# TraitementAnalogique.net
KiCad netlist of a schematic drawn in Altium Designer
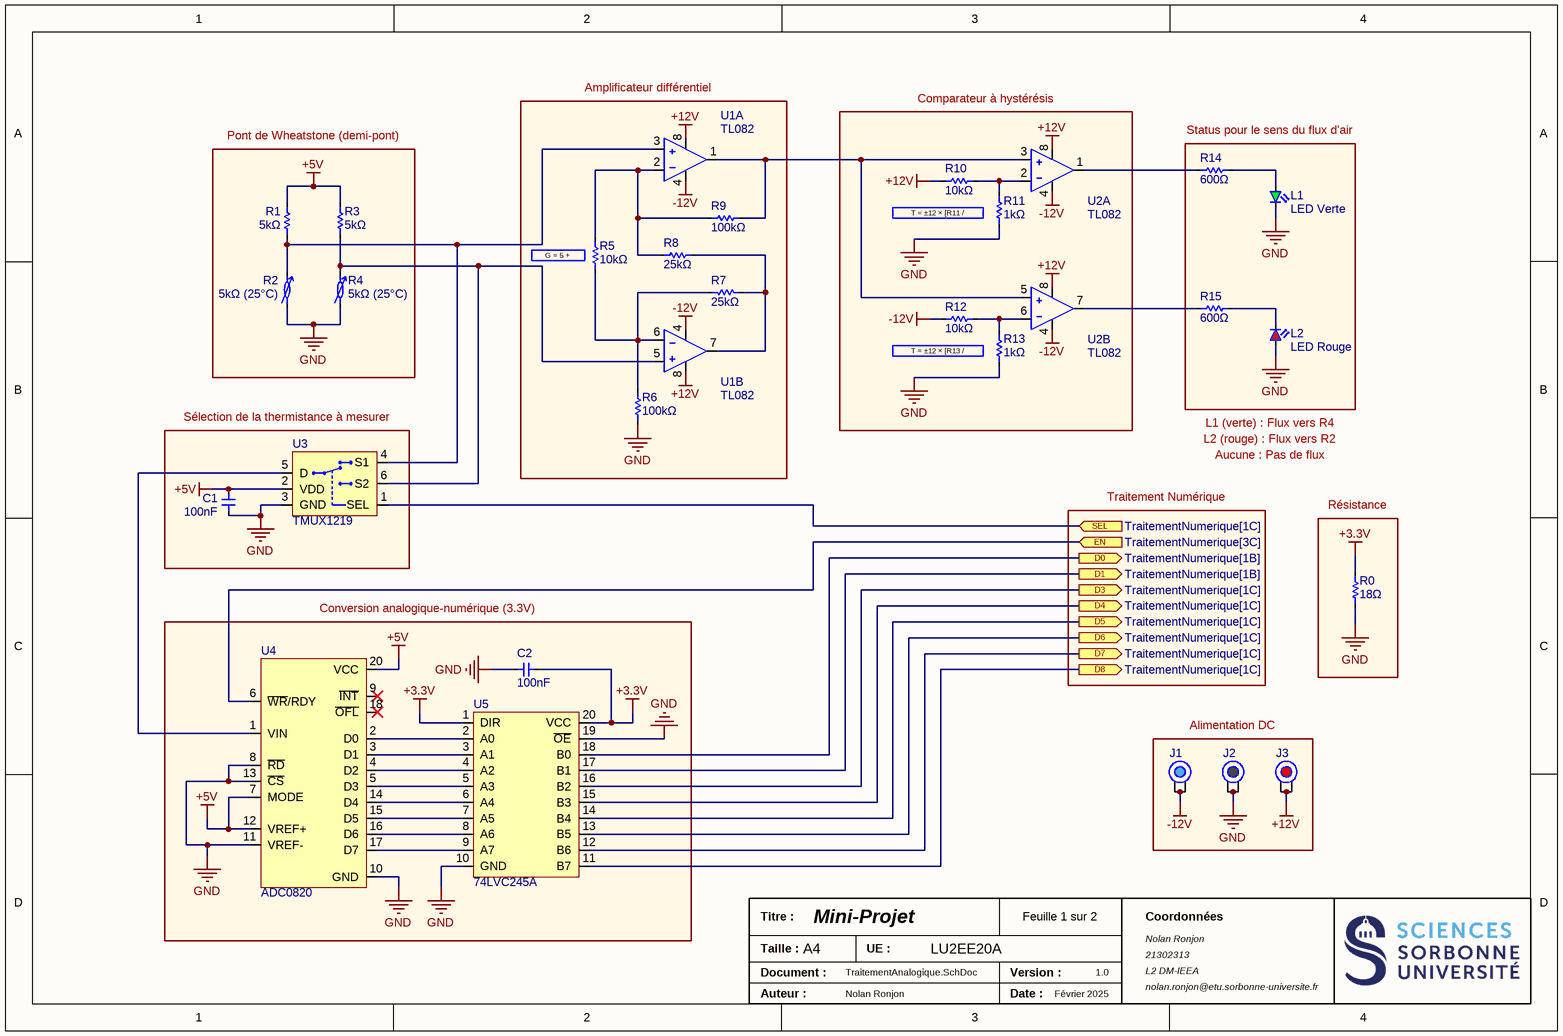
[diagram p0: TraitementAnalogique.SchDoc]

(export (version "E")
  (design (tool "Eeschema 10.0.6"))
  (components
    (comp (ref "C1")
      (value "100nF")
      (footprint "0603")
      (description "Condensateur")
      (libsource (lib "LU2EE20A") (part "Condensateur"))
    )
    (comp (ref "C2")
      (value "100nF")
      (footprint "0603")
      (description "Condensateur")
      (libsource (lib "LU2EE20A") (part "Condensateur"))
    )
    (comp (ref "J1")
      (value "Fiche Banane")
      (footprint "Fiche Banane")
      (description "Connecteur")
      (fields (field (name "MANUFACTURER PART") "24.243.5") (field (name "JLCPCB PART") "C7437325"))
      (libsource (lib "LU2EE20A") (part "Fiche Banane"))
    )
    (comp (ref "J2")
      (value "Fiche Banane")
      (footprint "Fiche Banane")
      (description "Connecteur")
      (fields (field (name "MANUFACTURER PART") "24.243.2") (field (name "JLCPCB PART") "C7437322"))
      (libsource (lib "LU2EE20A") (part "Fiche Banane"))
    )
    (comp (ref "J3")
      (value "Fiche Banane")
      (footprint "Fiche Banane")
      (description "Connecteur")
      (fields (field (name "MANUFACTURER PART") "24.243.1") (field (name "JLCPCB PART") "C7437321"))
      (libsource (lib "LU2EE20A") (part "Fiche Banane"))
    )
    (comp (ref "L1")
      (value "LED Verte")
      (footprint "0603 (Pol)")
      (description "LED")
      (fields (field (name "MANUFACTURER PART") "XL-1608UGC-04") (field (name "JLCPCB PART") "C965804"))
      (libsource (lib "LU2EE20A") (part "LED Verte"))
    )
    (comp (ref "L2")
      (value "LED Rouge")
      (footprint "0603 (Pol)")
      (description "LED")
      (fields (field (name "MANUFACTURER PART") "XL-1608SURC-06") (field (name "JLCPCB PART") "C965799"))
      (libsource (lib "LU2EE20A") (part "LED Rouge"))
    )
    (comp (ref "R0")
      (value "18Ω")
      (footprint "Bornier")
      (description "Resistance")
      (fields (field (name "MANUFACTURER PART") "WJ500V-5.08-2P") (field (name "JLCPCB PART") "C8465"))
      (libsource (lib "LU2EE20A") (part "Resistance"))
    )
    (comp (ref "R1")
      (value "5kΩ")
      (footprint "0603")
      (description "Resistance")
      (libsource (lib "LU2EE20A") (part "Resistance"))
    )
    (comp (ref "R2")
      (value "5kΩ (25°C)")
      (footprint "Bornier")
      (description "Thermistance")
      (fields (field (name "MANUFACTURER PART") "WJ500V-5.08-2P") (field (name "JLCPCB PART") "C8465"))
      (libsource (lib "LU2EE20A") (part "CTN"))
    )
    (comp (ref "R3")
      (value "5kΩ")
      (footprint "0603")
      (description "Resistance")
      (libsource (lib "LU2EE20A") (part "Resistance"))
    )
    (comp (ref "R4")
      (value "5kΩ (25°C)")
      (footprint "Bornier")
      (description "Thermistance")
      (fields (field (name "MANUFACTURER PART") "WJ500V-5.08-2P") (field (name "JLCPCB PART") "C8465"))
      (libsource (lib "LU2EE20A") (part "CTN"))
    )
    (comp (ref "R5")
      (value "10kΩ")
      (footprint "0603")
      (description "Resistance")
      (libsource (lib "LU2EE20A") (part "Resistance"))
    )
    (comp (ref "R6")
      (value "100kΩ")
      (footprint "0603")
      (description "Resistance")
      (libsource (lib "LU2EE20A") (part "Resistance"))
    )
    (comp (ref "R7")
      (value "25kΩ")
      (footprint "0603")
      (description "Resistance")
      (libsource (lib "LU2EE20A") (part "Resistance"))
    )
    (comp (ref "R8")
      (value "25kΩ")
      (footprint "0603")
      (description "Resistance")
      (libsource (lib "LU2EE20A") (part "Resistance"))
    )
    (comp (ref "R9")
      (value "100kΩ")
      (footprint "0603")
      (description "Resistance")
      (libsource (lib "LU2EE20A") (part "Resistance"))
    )
    (comp (ref "R10")
      (value "10kΩ")
      (footprint "0603")
      (description "Resistance")
      (libsource (lib "LU2EE20A") (part "Resistance"))
    )
    (comp (ref "R11")
      (value "1kΩ")
      (footprint "0603")
      (description "Resistance")
      (libsource (lib "LU2EE20A") (part "Resistance"))
    )
    (comp (ref "R12")
      (value "10kΩ")
      (footprint "0603")
      (description "Resistance")
      (libsource (lib "LU2EE20A") (part "Resistance"))
    )
    (comp (ref "R13")
      (value "1kΩ")
      (footprint "0603")
      (description "Resistance")
      (libsource (lib "LU2EE20A") (part "Resistance"))
    )
    (comp (ref "R14")
      (value "600Ω")
      (footprint "0603")
      (description "Resistance")
      (libsource (lib "LU2EE20A") (part "Resistance"))
    )
    (comp (ref "R15")
      (value "600Ω")
      (footprint "0603")
      (description "Resistance")
      (libsource (lib "LU2EE20A") (part "Resistance"))
    )
    (comp (ref "U1")
      (value "TL082")
      (footprint "SOIC-8")
      (description "AOP")
      (fields (field (name "MANUFACTURER PART") "TL082IDR") (field (name "JLCPCB PART") "C6966"))
      (libsource (lib "LU2EE20A") (part "TL082"))
    )
    (comp (ref "U2")
      (value "TL082")
      (footprint "SOIC-8")
      (description "AOP")
      (fields (field (name "MANUFACTURER PART") "TL082IDR") (field (name "JLCPCB PART") "C6966"))
      (libsource (lib "LU2EE20A") (part "TL082"))
    )
    (comp (ref "U3")
      (value "TMUX1219")
      (footprint "SOT-23-6")
      (description "Multiplexeur analogique")
      (fields (field (name "MANUFACTURER PART") "TMUX1219DBVR") (field (name "JLCPCB PART") "C2869838"))
      (libsource (lib "LU2EE20A") (part "TMUX1219"))
    )
    (comp (ref "U4")
      (value "ADC0820")
      (footprint "DIP-20")
      (description "CAN (8 bit)")
      (fields
        (field (name "MANUFACTURER PART") "DS1001-01-20BT1NSF6S-JKB")
        (field (name "JLCPCB PART") "C72127")
      )
      (libsource (lib "LU2EE20A") (part "ADC0820"))
    )
    (comp (ref "U5")
      (value "74LVC245A")
      (footprint "TSSOP-20")
      (description "Buffer bidirectionnel")
      (fields (field (name "MANUFACTURER PART") "SN74LVC245APWR") (field (name "JLCPCB PART") "C7848"))
      (libsource (lib "LU2EE20A") (part "74LVC245A"))
    )
  )
  (nets
    (net (code "1") (name "+3.3V") (class "Default")
      (node (ref "C2") (pin "2") (pinfunction "2_2") (pintype "passive"))
      (node (ref "R0") (pin "2") (pinfunction "2_2") (pintype "passive"))
      (node (ref "U5") (pin "1") (pinfunction "DIR_1") (pintype "passive"))
      (node (ref "U5") (pin "20") (pinfunction "VCC_20") (pintype "passive"))
    )
    (net (code "2") (name "+5V") (class "Default")
      (node (ref "C1") (pin "1") (pinfunction "1_1") (pintype "passive"))
      (node (ref "R1") (pin "2") (pinfunction "2_2") (pintype "passive"))
      (node (ref "R3") (pin "2") (pinfunction "2_2") (pintype "passive"))
      (node (ref "U3") (pin "2") (pinfunction "VDD_2") (pintype "passive"))
      (node (ref "U4") (pin "12") (pinfunction "VREF+_12") (pintype "passive"))
      (node (ref "U4") (pin "20") (pinfunction "VCC_20") (pintype "passive"))
      (node (ref "U4") (pin "7") (pinfunction "MODE_7") (pintype "passive"))
    )
    (net (code "3") (name "+12V") (class "Default")
      (node (ref "J3") (pin "1") (pinfunction "1_1") (pintype "passive"))
      (node (ref "J3") (pin "2") (pinfunction "2_2") (pintype "passive"))
      (node (ref "R10") (pin "2") (pinfunction "2_2") (pintype "passive"))
      (node (ref "U1") (pin "8") (pinfunction "VCC+_8") (pintype "passive"))
      (node (ref "U2") (pin "8") (pinfunction "VCC+_8") (pintype "passive"))
    )
    (net (code "4") (name "-12V") (class "Default")
      (node (ref "J1") (pin "1") (pinfunction "1_1") (pintype "passive"))
      (node (ref "J1") (pin "2") (pinfunction "2_2") (pintype "passive"))
      (node (ref "R12") (pin "2") (pinfunction "2_2") (pintype "passive"))
      (node (ref "U1") (pin "4") (pinfunction "VCC-_4") (pintype "passive"))
      (node (ref "U2") (pin "4") (pinfunction "VCC-_4") (pintype "passive"))
    )
    (net (code "5") (name "/D0") (class "Default")
      (node (ref "U5") (pin "18") (pinfunction "B0_18") (pintype "passive"))
    )
    (net (code "6") (name "/D1") (class "Default")
      (node (ref "U5") (pin "17") (pinfunction "B1_17") (pintype "passive"))
    )
    (net (code "7") (name "/D3") (class "Default")
      (node (ref "U5") (pin "16") (pinfunction "B2_16") (pintype "passive"))
    )
    (net (code "8") (name "/D4") (class "Default")
      (node (ref "U5") (pin "15") (pinfunction "B3_15") (pintype "passive"))
    )
    (net (code "9") (name "/D5") (class "Default")
      (node (ref "U5") (pin "14") (pinfunction "B4_14") (pintype "passive"))
    )
    (net (code "10") (name "/D6") (class "Default")
      (node (ref "U5") (pin "13") (pinfunction "B5_13") (pintype "passive"))
    )
    (net (code "11") (name "/D7") (class "Default")
      (node (ref "U5") (pin "12") (pinfunction "B6_12") (pintype "passive"))
    )
    (net (code "12") (name "/D8") (class "Default")
      (node (ref "U5") (pin "11") (pinfunction "B7_11") (pintype "passive"))
    )
    (net (code "13") (name "/EN") (class "Default")
      (node (ref "U4") (pin "6") (pinfunction "~{WR}/RDY_6") (pintype "passive"))
    )
    (net (code "14") (name "/SEL") (class "Default")
      (node (ref "U3") (pin "1") (pinfunction "SEL_1") (pintype "passive"))
    )
    (net (code "15") (name "GND") (class "Default")
      (node (ref "C1") (pin "2") (pinfunction "2_2") (pintype "passive"))
      (node (ref "C2") (pin "1") (pinfunction "1_1") (pintype "passive"))
      (node (ref "J2") (pin "1") (pinfunction "1_1") (pintype "passive"))
      (node (ref "J2") (pin "2") (pinfunction "2_2") (pintype "passive"))
      (node (ref "L1") (pin "2") (pinfunction "Cathode_2") (pintype "passive"))
      (node (ref "L2") (pin "1") (pinfunction "Anode_1") (pintype "passive"))
      (node (ref "R0") (pin "1") (pinfunction "1_1") (pintype "passive"))
      (node (ref "R11") (pin "1") (pinfunction "1_1") (pintype "passive"))
      (node (ref "R13") (pin "1") (pinfunction "1_1") (pintype "passive"))
      (node (ref "R2") (pin "1") (pinfunction "1_1") (pintype "passive"))
      (node (ref "R4") (pin "1") (pinfunction "1_1") (pintype "passive"))
      (node (ref "R6") (pin "1") (pinfunction "1_1") (pintype "passive"))
      (node (ref "U3") (pin "3") (pinfunction "GND_3") (pintype "passive"))
      (node (ref "U4") (pin "10") (pinfunction "GND_10") (pintype "passive"))
      (node (ref "U4") (pin "11") (pinfunction "VREF-_11") (pintype "passive"))
      (node (ref "U4") (pin "13") (pinfunction "CS_13") (pintype "passive"))
      (node (ref "U4") (pin "8") (pinfunction "RD_8") (pintype "passive"))
      (node (ref "U5") (pin "10") (pinfunction "GND_10") (pintype "passive"))
      (node (ref "U5") (pin "19") (pinfunction "OE_19") (pintype "passive"))
    )
    (net (code "16") (name "Net-(L1-Anode)") (class "Default")
      (node (ref "L1") (pin "1") (pinfunction "Anode_1") (pintype "passive"))
      (node (ref "R14") (pin "1") (pinfunction "1_1") (pintype "passive"))
    )
    (net (code "17") (name "Net-(L2-Cathode)") (class "Default")
      (node (ref "L2") (pin "2") (pinfunction "Cathode_2") (pintype "passive"))
      (node (ref "R15") (pin "1") (pinfunction "1_1") (pintype "passive"))
    )
    (net (code "18") (name "Net-(U1A-IN+)") (class "Default")
      (node (ref "R1") (pin "1") (pinfunction "1_1") (pintype "passive"))
      (node (ref "R2") (pin "2") (pinfunction "2_2") (pintype "passive"))
      (node (ref "U1") (pin "3") (pinfunction "IN+_3") (pintype "passive"))
      (node (ref "U3") (pin "4") (pinfunction "S1_4") (pintype "passive"))
    )
    (net (code "19") (name "Net-(U1A-IN-)") (class "Default")
      (node (ref "R5") (pin "2") (pinfunction "2_2") (pintype "passive"))
      (node (ref "R8") (pin "2") (pinfunction "2_2") (pintype "passive"))
      (node (ref "R9") (pin "2") (pinfunction "2_2") (pintype "passive"))
      (node (ref "U1") (pin "2") (pinfunction "IN-_2") (pintype "passive"))
    )
    (net (code "20") (name "Net-(U1A-OUT)") (class "Default")
      (node (ref "R9") (pin "1") (pinfunction "1_1") (pintype "passive"))
      (node (ref "U1") (pin "1") (pinfunction "OUT_1") (pintype "passive"))
      (node (ref "U2") (pin "3") (pinfunction "IN+_3") (pintype "passive"))
      (node (ref "U2") (pin "5") (pinfunction "IN+_5") (pintype "passive"))
    )
    (net (code "21") (name "Net-(U1B-IN+)") (class "Default")
      (node (ref "R3") (pin "1") (pinfunction "1_1") (pintype "passive"))
      (node (ref "R4") (pin "2") (pinfunction "2_2") (pintype "passive"))
      (node (ref "U1") (pin "5") (pinfunction "IN+_5") (pintype "passive"))
      (node (ref "U3") (pin "6") (pinfunction "S2_6") (pintype "passive"))
    )
    (net (code "22") (name "Net-(U1B-IN-)") (class "Default")
      (node (ref "R5") (pin "1") (pinfunction "1_1") (pintype "passive"))
      (node (ref "R6") (pin "2") (pinfunction "2_2") (pintype "passive"))
      (node (ref "R7") (pin "2") (pinfunction "2_2") (pintype "passive"))
      (node (ref "U1") (pin "6") (pinfunction "IN-_6") (pintype "passive"))
    )
    (net (code "23") (name "Net-(U1B-OUT)") (class "Default")
      (node (ref "R7") (pin "1") (pinfunction "1_1") (pintype "passive"))
      (node (ref "R8") (pin "1") (pinfunction "1_1") (pintype "passive"))
      (node (ref "U1") (pin "7") (pinfunction "OUT_7") (pintype "passive"))
    )
    (net (code "24") (name "Net-(U2A-IN-)") (class "Default")
      (node (ref "R10") (pin "1") (pinfunction "1_1") (pintype "passive"))
      (node (ref "R11") (pin "2") (pinfunction "2_2") (pintype "passive"))
      (node (ref "U2") (pin "2") (pinfunction "IN-_2") (pintype "passive"))
    )
    (net (code "25") (name "Net-(U2A-OUT)") (class "Default")
      (node (ref "R14") (pin "2") (pinfunction "2_2") (pintype "passive"))
      (node (ref "U2") (pin "1") (pinfunction "OUT_1") (pintype "passive"))
    )
    (net (code "26") (name "Net-(U2B-IN-)") (class "Default")
      (node (ref "R12") (pin "1") (pinfunction "1_1") (pintype "passive"))
      (node (ref "R13") (pin "2") (pinfunction "2_2") (pintype "passive"))
      (node (ref "U2") (pin "6") (pinfunction "IN-_6") (pintype "passive"))
    )
    (net (code "27") (name "Net-(U2B-OUT)") (class "Default")
      (node (ref "R15") (pin "2") (pinfunction "2_2") (pintype "passive"))
      (node (ref "U2") (pin "7") (pinfunction "OUT_7") (pintype "passive"))
    )
    (net (code "28") (name "Net-(U3-D)") (class "Default")
      (node (ref "U3") (pin "5") (pinfunction "D_5") (pintype "passive"))
      (node (ref "U4") (pin "1") (pinfunction "VIN_1") (pintype "passive"))
    )
    (net (code "29") (name "Net-(U4-D0)") (class "Default")
      (node (ref "U4") (pin "2") (pinfunction "D0_2") (pintype "passive"))
      (node (ref "U5") (pin "2") (pinfunction "A0_2") (pintype "passive"))
    )
    (net (code "30") (name "Net-(U4-D1)") (class "Default")
      (node (ref "U4") (pin "3") (pinfunction "D1_3") (pintype "passive"))
      (node (ref "U5") (pin "3") (pinfunction "A1_3") (pintype "passive"))
    )
    (net (code "31") (name "Net-(U4-D2)") (class "Default")
      (node (ref "U4") (pin "4") (pinfunction "D2_4") (pintype "passive"))
      (node (ref "U5") (pin "4") (pinfunction "A2_4") (pintype "passive"))
    )
    (net (code "32") (name "Net-(U4-D3)") (class "Default")
      (node (ref "U4") (pin "5") (pinfunction "D3_5") (pintype "passive"))
      (node (ref "U5") (pin "5") (pinfunction "A3_5") (pintype "passive"))
    )
    (net (code "33") (name "Net-(U4-D4)") (class "Default")
      (node (ref "U4") (pin "14") (pinfunction "D4_14") (pintype "passive"))
      (node (ref "U5") (pin "6") (pinfunction "A4_6") (pintype "passive"))
    )
    (net (code "34") (name "Net-(U4-D5)") (class "Default")
      (node (ref "U4") (pin "15") (pinfunction "D5_15") (pintype "passive"))
      (node (ref "U5") (pin "7") (pinfunction "A5_7") (pintype "passive"))
    )
    (net (code "35") (name "Net-(U4-D6)") (class "Default")
      (node (ref "U4") (pin "16") (pinfunction "D6_16") (pintype "passive"))
      (node (ref "U5") (pin "8") (pinfunction "A6_8") (pintype "passive"))
    )
    (net (code "36") (name "Net-(U4-D7)") (class "Default")
      (node (ref "U4") (pin "17") (pinfunction "D7_17") (pintype "passive"))
      (node (ref "U5") (pin "9") (pinfunction "A7_9") (pintype "passive"))
    )
    (net (code "37") (name "unconnected-(U4-INT-Pad9)") (class "Default")
      (node (ref "U4") (pin "9") (pinfunction "INT_9") (pintype "passive+no_connect"))
    )
    (net (code "38") (name "unconnected-(U4-OFL-Pad18)") (class "Default")
      (node (ref "U4") (pin "18") (pinfunction "OFL_18") (pintype "passive+no_connect"))
    )
  )
)
